# 20A_Motor_Controller.net
KiCad netlist of a schematic drawn in EAGLE
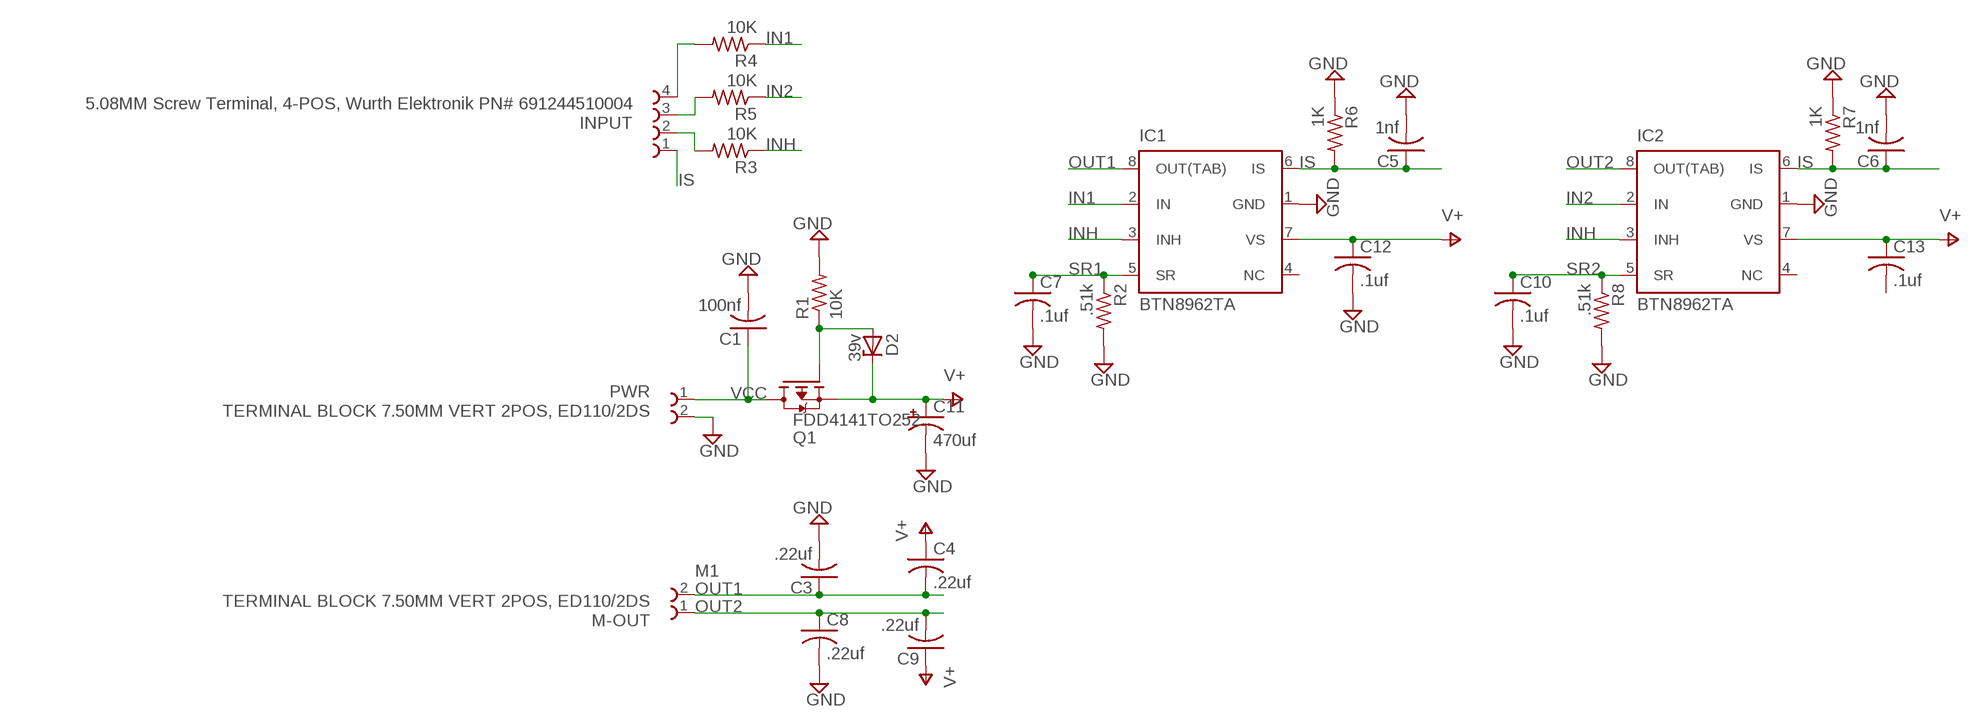
[diagram p0: schematic, sheet 1]

(export (version "E")
  (design (tool "Eeschema 10.0.6"))
  (components
    (comp (ref "C1")
      (value "100nf")
      (footprint "eagle-import:C0805")
      (libsource (lib "eagle-import") (part "C-USC0805"))
    )
    (comp (ref "C3")
      (value ".22uf")
      (footprint "eagle-import:C0805")
      (libsource (lib "eagle-import") (part "C-USC0805"))
    )
    (comp (ref "C4")
      (value ".22uf")
      (footprint "eagle-import:C0805")
      (libsource (lib "eagle-import") (part "C-USC0805"))
    )
    (comp (ref "C5")
      (value "1nf")
      (footprint "eagle-import:C0805")
      (libsource (lib "eagle-import") (part "C-USC0805"))
    )
    (comp (ref "C6")
      (value "1nf")
      (footprint "eagle-import:C0805")
      (libsource (lib "eagle-import") (part "C-USC0805"))
    )
    (comp (ref "C7")
      (value ".1uf")
      (footprint "eagle-import:C0805")
      (libsource (lib "eagle-import") (part "C-USC0805"))
    )
    (comp (ref "C8")
      (value ".22uf")
      (footprint "eagle-import:C0805")
      (libsource (lib "eagle-import") (part "C-USC0805"))
    )
    (comp (ref "C9")
      (value ".22uf")
      (footprint "eagle-import:C0805")
      (libsource (lib "eagle-import") (part "C-USC0805"))
    )
    (comp (ref "C10")
      (value ".1uf")
      (footprint "eagle-import:C0805")
      (libsource (lib "eagle-import") (part "C-USC0805"))
    )
    (comp (ref "C11")
      (value "470uf")
      (footprint "eagle-import:TT5D10")
      (libsource (lib "eagle-import") (part "CPOL-USTT5D10"))
    )
    (comp (ref "C12")
      (value ".1uf")
      (footprint "eagle-import:C0805")
      (libsource (lib "eagle-import") (part "C-USC0805"))
    )
    (comp (ref "C13")
      (value ".1uf")
      (footprint "eagle-import:C0805")
      (libsource (lib "eagle-import") (part "C-USC0805"))
    )
    (comp (ref "D2")
      (value "39v")
      (footprint "eagle-import:SMB")
      (libsource (lib "eagle-import") (part "ZENER-DIODESMB"))
    )
    (comp (ref "IC1")
      (value "BTN8962TA")
      (footprint "eagle-import:P-TO263-7-1_LG_PADS")
      (libsource (lib "eagle-import") (part "BTN8962TA"))
    )
    (comp (ref "IC2")
      (value "BTN8962TA")
      (footprint "eagle-import:P-TO263-7-1_LG_PADS")
      (libsource (lib "eagle-import") (part "BTN8962TA"))
    )
    (comp (ref "INPUT")
      (value "5.08MM Screw Terminal, 4-POS, Wurth Elektronik PN# 691244510004")
      (footprint "eagle-import:691244510004")
      (libsource (lib "eagle-import") (part "691244510004"))
    )
    (comp (ref "M-OUT")
      (value "TERMINAL BLOCK 7.50MM VERT 2POS, ED110/2DS")
      (footprint "eagle-import:7-5MM-SCREW-TERM")
      (libsource (lib "eagle-import") (part "7-5MM-SCREW-TERM"))
    )
    (comp (ref "PWR")
      (value "TERMINAL BLOCK 7.50MM VERT 2POS, ED110/2DS")
      (footprint "eagle-import:7-5MM-SCREW-TERM")
      (libsource (lib "eagle-import") (part "7-5MM-SCREW-TERM"))
    )
    (comp (ref "Q1")
      (value "FDD4141TO252")
      (footprint "eagle-import:TO252")
      (libsource (lib "eagle-import") (part "FDD4141TO252"))
    )
    (comp (ref "R1")
      (value "10K")
      (footprint "eagle-import:R0805")
      (libsource (lib "eagle-import") (part "R-US_R0805"))
    )
    (comp (ref "R2")
      (value ".51k")
      (footprint "eagle-import:R0805")
      (libsource (lib "eagle-import") (part "R-US_R0805"))
    )
    (comp (ref "R3")
      (value "10K")
      (footprint "eagle-import:R0805")
      (libsource (lib "eagle-import") (part "R-US_R0805"))
    )
    (comp (ref "R4")
      (value "10K")
      (footprint "eagle-import:R0805")
      (libsource (lib "eagle-import") (part "R-US_R0805"))
    )
    (comp (ref "R5")
      (value "10K")
      (footprint "eagle-import:R0805")
      (libsource (lib "eagle-import") (part "R-US_R0805"))
    )
    (comp (ref "R6")
      (value "1K")
      (footprint "eagle-import:R0805")
      (libsource (lib "eagle-import") (part "R-US_R0805"))
    )
    (comp (ref "R7")
      (value "1K")
      (footprint "eagle-import:R0805")
      (libsource (lib "eagle-import") (part "R-US_R0805"))
    )
    (comp (ref "R8")
      (value ".51k")
      (footprint "eagle-import:R0805")
      (libsource (lib "eagle-import") (part "R-US_R0805"))
    )
  )
  (nets
    (net (code "1") (name "/IN1") (class "Default")
      (node (ref "IC1") (pin "2") (pinfunction "IN_2") (pintype "input"))
      (node (ref "R4") (pin "1") (pinfunction "1_1") (pintype "passive"))
    )
    (net (code "2") (name "/IN2") (class "Default")
      (node (ref "IC2") (pin "2") (pinfunction "IN_2") (pintype "input"))
      (node (ref "R5") (pin "1") (pinfunction "1_1") (pintype "passive"))
    )
    (net (code "3") (name "/INH") (class "Default")
      (node (ref "IC1") (pin "3") (pinfunction "INH_3") (pintype "input"))
      (node (ref "IC2") (pin "3") (pinfunction "INH_3") (pintype "input"))
      (node (ref "R3") (pin "1") (pinfunction "1_1") (pintype "passive"))
    )
    (net (code "4") (name "/IS") (class "Default")
      (node (ref "C5") (pin "1") (pinfunction "1_1") (pintype "passive"))
      (node (ref "C6") (pin "1") (pinfunction "1_1") (pintype "passive"))
      (node (ref "IC1") (pin "6") (pinfunction "IS_6") (pintype "output"))
      (node (ref "IC2") (pin "6") (pinfunction "IS_6") (pintype "output"))
      (node (ref "INPUT") (pin "1") (pinfunction "1_1") (pintype "passive"))
      (node (ref "R6") (pin "2") (pinfunction "2_2") (pintype "passive"))
      (node (ref "R7") (pin "2") (pinfunction "2_2") (pintype "passive"))
    )
    (net (code "5") (name "/OUT1") (class "Default")
      (node (ref "C3") (pin "1") (pinfunction "1_1") (pintype "passive"))
      (node (ref "C4") (pin "2") (pinfunction "2_2") (pintype "passive"))
      (node (ref "IC1") (pin "8") (pinfunction "OUT(TAB)_8") (pintype "output"))
      (node (ref "M-OUT") (pin "2") (pinfunction "2_2") (pintype "passive"))
    )
    (net (code "6") (name "/OUT2") (class "Default")
      (node (ref "C8") (pin "1") (pinfunction "1_1") (pintype "passive"))
      (node (ref "C9") (pin "2") (pinfunction "2_2") (pintype "passive"))
      (node (ref "IC2") (pin "8") (pinfunction "OUT(TAB)_8") (pintype "output"))
      (node (ref "M-OUT") (pin "1") (pinfunction "1_1") (pintype "passive"))
    )
    (net (code "7") (name "/SR1") (class "Default")
      (node (ref "C7") (pin "1") (pinfunction "1_1") (pintype "passive"))
      (node (ref "IC1") (pin "5") (pinfunction "SR_5") (pintype "input"))
      (node (ref "R2") (pin "1") (pinfunction "1_1") (pintype "passive"))
    )
    (net (code "8") (name "/SR2") (class "Default")
      (node (ref "C10") (pin "1") (pinfunction "1_1") (pintype "passive"))
      (node (ref "IC2") (pin "5") (pinfunction "SR_5") (pintype "input"))
      (node (ref "R8") (pin "1") (pinfunction "1_1") (pintype "passive"))
    )
    (net (code "9") (name "/VCC") (class "Default")
      (node (ref "C1") (pin "1") (pinfunction "1_1") (pintype "passive"))
      (node (ref "PWR") (pin "1") (pinfunction "1_1") (pintype "passive"))
      (node (ref "Q1") (pin "3") (pinfunction "D_3") (pintype "passive"))
    )
    (net (code "10") (name "GND") (class "Default")
      (node (ref "C1") (pin "2") (pinfunction "2_2") (pintype "passive"))
      (node (ref "C10") (pin "2") (pinfunction "2_2") (pintype "passive"))
      (node (ref "C11") (pin "-") (pinfunction "-_-") (pintype "passive"))
      (node (ref "C12") (pin "2") (pinfunction "2_2") (pintype "passive"))
      (node (ref "C3") (pin "2") (pinfunction "2_2") (pintype "passive"))
      (node (ref "C5") (pin "2") (pinfunction "2_2") (pintype "passive"))
      (node (ref "C6") (pin "2") (pinfunction "2_2") (pintype "passive"))
      (node (ref "C7") (pin "2") (pinfunction "2_2") (pintype "passive"))
      (node (ref "C8") (pin "2") (pinfunction "2_2") (pintype "passive"))
      (node (ref "IC1") (pin "1") (pinfunction "GND_1") (pintype "power_in"))
      (node (ref "IC2") (pin "1") (pinfunction "GND_1") (pintype "power_in"))
      (node (ref "PWR") (pin "2") (pinfunction "2_2") (pintype "passive"))
      (node (ref "R1") (pin "2") (pinfunction "2_2") (pintype "passive"))
      (node (ref "R2") (pin "2") (pinfunction "2_2") (pintype "passive"))
      (node (ref "R6") (pin "1") (pinfunction "1_1") (pintype "passive"))
      (node (ref "R7") (pin "1") (pinfunction "1_1") (pintype "passive"))
      (node (ref "R8") (pin "2") (pinfunction "2_2") (pintype "passive"))
    )
    (net (code "11") (name "Net-(INPUT-Pad2)") (class "Default")
      (node (ref "INPUT") (pin "2") (pinfunction "2_2") (pintype "passive"))
      (node (ref "R3") (pin "2") (pinfunction "2_2") (pintype "passive"))
    )
    (net (code "12") (name "Net-(INPUT-Pad3)") (class "Default")
      (node (ref "INPUT") (pin "3") (pinfunction "3_3") (pintype "passive"))
      (node (ref "R5") (pin "2") (pinfunction "2_2") (pintype "passive"))
    )
    (net (code "13") (name "Net-(INPUT-Pad4)") (class "Default")
      (node (ref "INPUT") (pin "4") (pinfunction "4_4") (pintype "passive"))
      (node (ref "R4") (pin "2") (pinfunction "2_2") (pintype "passive"))
    )
    (net (code "14") (name "Net-(Q1-G)") (class "Default")
      (node (ref "D2") (pin "A") (pinfunction "A_A") (pintype "passive"))
      (node (ref "Q1") (pin "1") (pinfunction "G_1") (pintype "passive"))
      (node (ref "R1") (pin "1") (pinfunction "1_1") (pintype "passive"))
    )
    (net (code "15") (name "V+") (class "Default")
      (node (ref "C11") (pin "+") (pinfunction "+_+") (pintype "passive"))
      (node (ref "C12") (pin "1") (pinfunction "1_1") (pintype "passive"))
      (node (ref "C13") (pin "1") (pinfunction "1_1") (pintype "passive"))
      (node (ref "C4") (pin "1") (pinfunction "1_1") (pintype "passive"))
      (node (ref "C9") (pin "1") (pinfunction "1_1") (pintype "passive"))
      (node (ref "D2") (pin "C") (pinfunction "C_C") (pintype "passive"))
      (node (ref "IC1") (pin "7") (pinfunction "VS_7") (pintype "power_in"))
      (node (ref "IC2") (pin "7") (pinfunction "VS_7") (pintype "power_in"))
      (node (ref "Q1") (pin "2") (pinfunction "S_2") (pintype "passive"))
    )
    (net (code "16") (name "unconnected-(C13-Pad2)") (class "Default")
      (node (ref "C13") (pin "2") (pinfunction "2_2") (pintype "passive"))
    )
    (net (code "17") (name "unconnected-(IC1-NC-Pad4)") (class "Default")
      (node (ref "IC1") (pin "4") (pinfunction "NC_4") (pintype "no_connect"))
    )
    (net (code "18") (name "unconnected-(IC2-NC-Pad4)") (class "Default")
      (node (ref "IC2") (pin "4") (pinfunction "NC_4") (pintype "no_connect"))
    )
  )
)
